# 1_AS5600_schdoc.net
KiCad netlist of a schematic drawn in Altium Designer
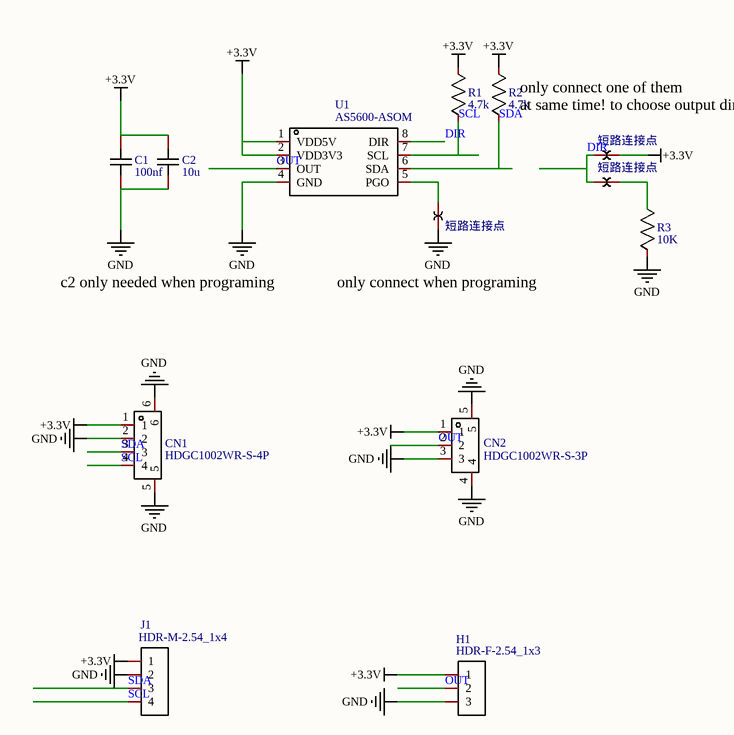
[diagram p0: 1_AS5600.schdoc.schdoc]

(export (version "E")
  (design (tool "Eeschema 10.0.6"))
  (components
    (comp (ref "C1")
      (value "100nf")
      (fields (field (name "NAME") "100nf"))
      (libsource (lib "altium-import") (part "root_1_100nf_"))
    )
    (comp (ref "C2")
      (value "10u")
      (fields (field (name "NAME") "10u"))
      (libsource (lib "altium-import") (part "root_1_10u_"))
    )
    (comp (ref "CN1")
      (value "HDGC1002WR-S-4P")
      (fields (field (name "NAME") "HDGC1002WR-S-4P") (field (name "MANUFACTURER") "HDGC(华德共创)"))
      (libsource (lib "altium-import") (part "root_0_HDGC1002WR-S-4P_"))
    )
    (comp (ref "CN2")
      (value "HDGC1002WR-S-3P")
      (fields (field (name "NAME") "HDGC1002WR-S-3P") (field (name "MANUFACTURER") "HDGC(华德共创)"))
      (libsource (lib "altium-import") (part "root_0_HDGC1002WR-S-3P_"))
    )
    (comp (ref "H1")
      (value "HDR-F-2.54_1x3")
      (fields (field (name "NAME") "HDR-F-2.54_1x3"))
      (libsource (lib "altium-import") (part "root_0_HDR-F-2.54_1x3_"))
    )
    (comp (ref "J1")
      (value "HDR-M-2.54_1x4")
      (fields (field (name "NAME") "HDR-M-2.54_1x4"))
      (libsource (lib "altium-import") (part "root_0_HDR-M-2.54_1x4_"))
    )
    (comp (ref "NO1")
      (value "短路连接点")
      (fields (field (name "NAME") "短路连接点"))
      (libsource (lib "altium-import") (part "root_1_短路连接点_"))
    )
    (comp (ref "NO2")
      (value "短路连接点")
      (fields (field (name "NAME") "短路连接点"))
      (libsource (lib "altium-import") (part "root_0_短路连接点_"))
    )
    (comp (ref "NO3")
      (value "短路连接点")
      (fields (field (name "NAME") "短路连接点"))
      (libsource (lib "altium-import") (part "root_0_短路连接点_"))
    )
    (comp (ref "R1")
      (value "4.7k")
      (fields (field (name "NAME") "4.7k"))
      (libsource (lib "altium-import") (part "root_1_4.7k_"))
    )
    (comp (ref "R2")
      (value "4.7k")
      (fields (field (name "NAME") "4.7k"))
      (libsource (lib "altium-import") (part "root_1_4.7k_"))
    )
    (comp (ref "R3")
      (value "10K")
      (fields (field (name "NAME") "10K"))
      (libsource (lib "altium-import") (part "root_1_10K_"))
    )
    (comp (ref "U1")
      (value "AS5600-ASOM")
      (fields (field (name "NAME") "AS5600-ASOM") (field (name "MANUFACTURER") "Ams"))
      (libsource (lib "altium-import") (part "root_0_AS5600-ASOM_"))
    )
  )
  (nets
    (net (code "1") (name "+3.3V") (class "Default")
      (node (ref "C1") (pin "2") (pinfunction "2_2") (pintype "passive"))
      (node (ref "C2") (pin "2") (pinfunction "2_2") (pintype "passive"))
      (node (ref "CN1") (pin "1") (pinfunction "1_1") (pintype "passive"))
      (node (ref "CN2") (pin "1") (pinfunction "1_1") (pintype "passive"))
      (node (ref "H1") (pin "1") (pinfunction "1_1") (pintype "passive"))
      (node (ref "J1") (pin "1") (pinfunction "1_1") (pintype "passive"))
      (node (ref "NO3") (pin "1") (pinfunction "1_1") (pintype "passive"))
      (node (ref "R1") (pin "2") (pinfunction "2_2") (pintype "passive"))
      (node (ref "R2") (pin "2") (pinfunction "2_2") (pintype "passive"))
      (node (ref "U1") (pin "1") (pinfunction "VDD5V_1") (pintype "passive"))
      (node (ref "U1") (pin "2") (pinfunction "VDD3V3_2") (pintype "passive"))
    )
    (net (code "2") (name "/DIR") (class "Default")
      (node (ref "NO2") (pin "2") (pinfunction "2_2") (pintype "passive"))
      (node (ref "NO3") (pin "2") (pinfunction "2_2") (pintype "passive"))
      (node (ref "U1") (pin "8") (pinfunction "DIR_8") (pintype "passive"))
    )
    (net (code "3") (name "/OUT") (class "Default")
      (node (ref "CN2") (pin "2") (pinfunction "2_2") (pintype "passive"))
      (node (ref "H1") (pin "2") (pinfunction "2_2") (pintype "passive"))
      (node (ref "U1") (pin "3") (pinfunction "OUT_3") (pintype "passive"))
    )
    (net (code "4") (name "/SCL") (class "Default")
      (node (ref "CN1") (pin "4") (pinfunction "4_4") (pintype "passive"))
      (node (ref "J1") (pin "4") (pinfunction "4_4") (pintype "passive"))
      (node (ref "R1") (pin "1") (pinfunction "1_1") (pintype "passive"))
      (node (ref "U1") (pin "7") (pinfunction "SCL_7") (pintype "passive"))
    )
    (net (code "5") (name "/SDA") (class "Default")
      (node (ref "CN1") (pin "3") (pinfunction "3_3") (pintype "passive"))
      (node (ref "J1") (pin "3") (pinfunction "3_3") (pintype "passive"))
      (node (ref "R2") (pin "1") (pinfunction "1_1") (pintype "passive"))
      (node (ref "U1") (pin "6") (pinfunction "SDA_6") (pintype "passive"))
    )
    (net (code "6") (name "GND") (class "Default")
      (node (ref "C1") (pin "1") (pinfunction "1_1") (pintype "passive"))
      (node (ref "C2") (pin "1") (pinfunction "1_1") (pintype "passive"))
      (node (ref "CN1") (pin "2") (pinfunction "2_2") (pintype "passive"))
      (node (ref "CN1") (pin "5") (pinfunction "5_5") (pintype "passive"))
      (node (ref "CN1") (pin "6") (pinfunction "6_6") (pintype "passive"))
      (node (ref "CN2") (pin "3") (pinfunction "3_3") (pintype "passive"))
      (node (ref "CN2") (pin "4") (pinfunction "4_4") (pintype "passive"))
      (node (ref "CN2") (pin "5") (pinfunction "5_5") (pintype "passive"))
      (node (ref "H1") (pin "3") (pinfunction "3_3") (pintype "passive"))
      (node (ref "J1") (pin "2") (pinfunction "2_2") (pintype "passive"))
      (node (ref "NO1") (pin "2") (pinfunction "2_2") (pintype "passive"))
      (node (ref "R3") (pin "1") (pinfunction "1_1") (pintype "passive"))
      (node (ref "U1") (pin "4") (pinfunction "GND_4") (pintype "passive"))
    )
    (net (code "7") (name "Net-(NO2-Pad1)") (class "Default")
      (node (ref "NO2") (pin "1") (pinfunction "1_1") (pintype "passive"))
      (node (ref "R3") (pin "2") (pinfunction "2_2") (pintype "passive"))
    )
    (net (code "8") (name "Net-(U1-PGO)") (class "Default")
      (node (ref "NO1") (pin "1") (pinfunction "1_1") (pintype "passive"))
      (node (ref "U1") (pin "5") (pinfunction "PGO_5") (pintype "passive"))
    )
  )
)
